# Xedk.net
KiCad netlist of a schematic drawn in Altium Designer
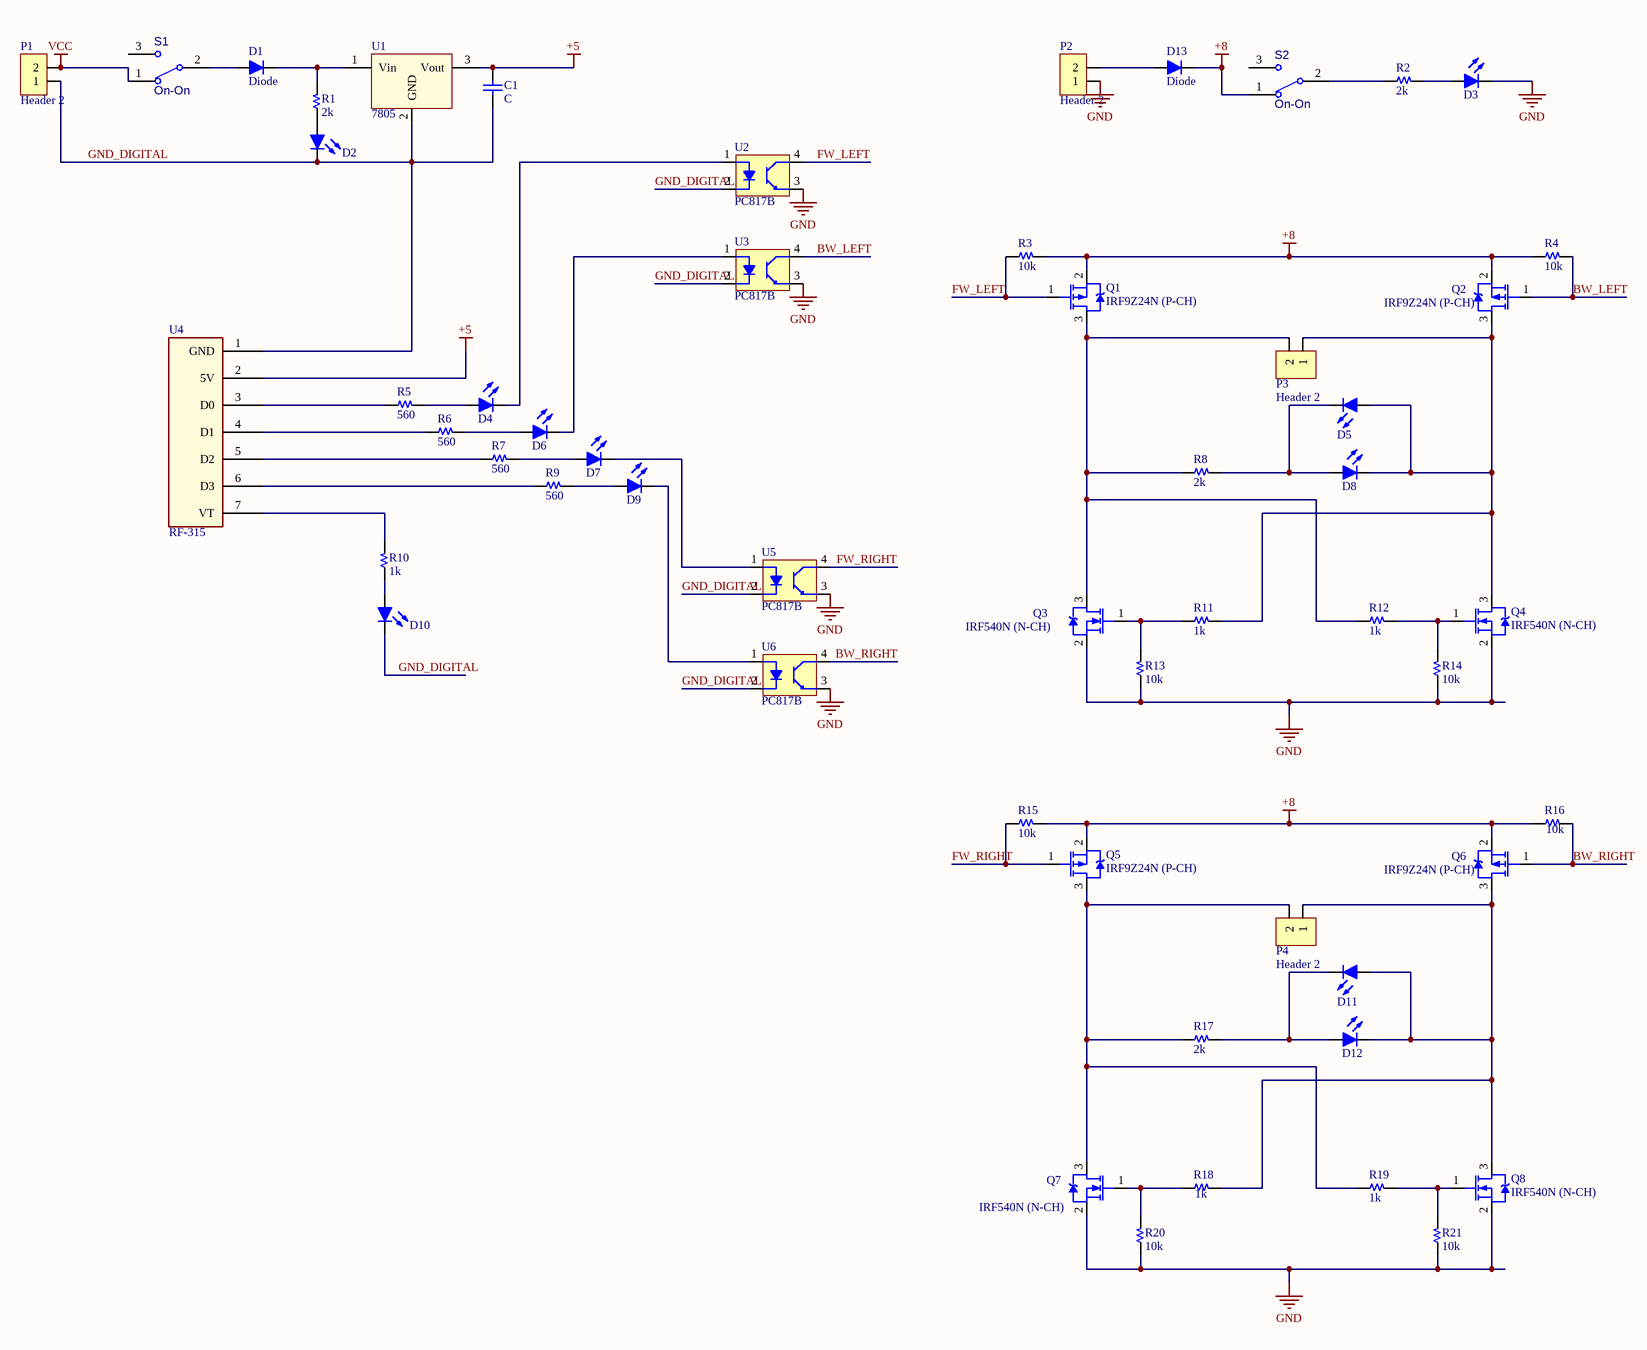
[diagram p0: Xedk.SchDoc]

(export (version "E")
  (design (tool "Eeschema 10.0.6"))
  (components
    (comp (ref "C1")
      (value "C")
      (footprint "CAP Ceramic/W300")
      (description "Capacitor non-pol")
      (libsource (lib "IntLib_Xedk") (part "Capacitor NP"))
    )
    (comp (ref "D1")
      (value "Diode")
      (footprint "DO-41")
      (description "Default Diode")
      (libsource (lib "IntLib_Xedk") (part "Diode"))
    )
    (comp (ref "D2")
      (value "Led")
      (footprint "LED 5MM - GREEN")
      (description "Typical LED")
      (libsource (lib "IntLib_Xedk") (part "Led"))
    )
    (comp (ref "D3")
      (value "Led")
      (footprint "LED 5MM - GREEN")
      (description "Typical LED")
      (libsource (lib "IntLib_Xedk") (part "Led"))
    )
    (comp (ref "D4")
      (value "Led")
      (footprint "LED 5MM - RED")
      (description "Typical LED")
      (libsource (lib "IntLib_Xedk") (part "Led"))
    )
    (comp (ref "D5")
      (value "Led")
      (footprint "LED 5MM - RED")
      (description "Typical LED")
      (libsource (lib "IntLib_Xedk") (part "Led"))
    )
    (comp (ref "D6")
      (value "Led")
      (footprint "LED 5MM - RED")
      (description "Typical LED")
      (libsource (lib "IntLib_Xedk") (part "Led"))
    )
    (comp (ref "D7")
      (value "Led")
      (footprint "LED 5MM - RED")
      (description "Typical LED")
      (libsource (lib "IntLib_Xedk") (part "Led"))
    )
    (comp (ref "D8")
      (value "Led")
      (footprint "LED 5MM - GREEN")
      (description "Typical LED")
      (libsource (lib "IntLib_Xedk") (part "Led"))
    )
    (comp (ref "D9")
      (value "Led")
      (footprint "LED 5MM - RED")
      (description "Typical LED")
      (libsource (lib "IntLib_Xedk") (part "Led"))
    )
    (comp (ref "D10")
      (value "Led")
      (footprint "LED 5MM - RED")
      (description "Typical LED")
      (libsource (lib "IntLib_Xedk") (part "Led"))
    )
    (comp (ref "D11")
      (value "Led")
      (footprint "LED 5MM - RED")
      (description "Typical LED")
      (libsource (lib "IntLib_Xedk") (part "Led"))
    )
    (comp (ref "D12")
      (value "Led")
      (footprint "LED 5MM - GREEN")
      (description "Typical LED")
      (libsource (lib "IntLib_Xedk") (part "Led"))
    )
    (comp (ref "D13")
      (value "Diode")
      (footprint "DO-41")
      (description "Default Diode")
      (libsource (lib "IntLib_Xedk") (part "Diode"))
    )
    (comp (ref "P1")
      (value "Header 2")
      (footprint "HDR/Terminal/2/5mm")
      (description "Header, 2-Pin")
      (libsource (lib "") (part "Header 2_1"))
    )
    (comp (ref "P2")
      (value "Header 2")
      (footprint "HDR/Terminal/2/5mm")
      (description "Header, 2-Pin")
      (libsource (lib "") (part "Header 2_1"))
    )
    (comp (ref "P3")
      (value "Header 2")
      (footprint "HDR/Terminal/2/5mm")
      (description "Header, 2-Pin")
      (libsource (lib "IntLib_Xedk") (part "Header 2"))
    )
    (comp (ref "P4")
      (value "Header 2")
      (footprint "HDR/Terminal/2/5mm")
      (description "Header, 2-Pin")
      (libsource (lib "IntLib_Xedk") (part "Header 2"))
    )
    (comp (ref "Q1")
      (value "IRF9Z24N (P-CH)")
      (footprint "TO-220")
      (description "Mosfet P")
      (libsource (lib "IntLib_Xedk") (part "Mosfet P"))
    )
    (comp (ref "Q2")
      (value "IRF9Z24N (P-CH)")
      (footprint "TO-220")
      (description "Mosfet P")
      (libsource (lib "IntLib_Xedk") (part "Mosfet P"))
    )
    (comp (ref "Q3")
      (value "IRF540N (N-CH)")
      (footprint "TO-220")
      (description "Mosfet N")
      (libsource (lib "IntLib_Xedk") (part "Mosfet N"))
    )
    (comp (ref "Q4")
      (value "IRF540N (N-CH)")
      (footprint "TO-220")
      (description "Mosfet N")
      (libsource (lib "IntLib_Xedk") (part "Mosfet N"))
    )
    (comp (ref "Q5")
      (value "IRF9Z24N (P-CH)")
      (footprint "TO-220")
      (description "Mosfet P")
      (libsource (lib "IntLib_Xedk") (part "Mosfet P"))
    )
    (comp (ref "Q6")
      (value "IRF9Z24N (P-CH)")
      (footprint "TO-220")
      (description "Mosfet P")
      (libsource (lib "IntLib_Xedk") (part "Mosfet P"))
    )
    (comp (ref "Q7")
      (value "IRF540N (N-CH)")
      (footprint "TO-220")
      (description "Mosfet N")
      (libsource (lib "IntLib_Xedk") (part "Mosfet N"))
    )
    (comp (ref "Q8")
      (value "IRF540N (N-CH)")
      (footprint "TO-220")
      (description "Mosfet N")
      (libsource (lib "IntLib_Xedk") (part "Mosfet N"))
    )
    (comp (ref "R1")
      (value "2k")
      (footprint "R 1/4W/300")
      (description "Resistor")
      (libsource (lib "IntLib_Xedk") (part "Resistor"))
    )
    (comp (ref "R2")
      (value "2k")
      (footprint "R 1/4W/300")
      (description "Resistor")
      (libsource (lib "IntLib_Xedk") (part "Resistor"))
    )
    (comp (ref "R3")
      (value "10k")
      (footprint "R 1/4W/300")
      (description "Resistor")
      (libsource (lib "IntLib_Xedk") (part "Resistor"))
    )
    (comp (ref "R4")
      (value "10k")
      (footprint "R 1/4W/300")
      (description "Resistor")
      (libsource (lib "IntLib_Xedk") (part "Resistor"))
    )
    (comp (ref "R5")
      (value "560")
      (footprint "R 1/4W/300")
      (description "Resistor")
      (libsource (lib "IntLib_Xedk") (part "Resistor"))
    )
    (comp (ref "R6")
      (value "560")
      (footprint "R 1/4W/300")
      (description "Resistor")
      (libsource (lib "IntLib_Xedk") (part "Resistor"))
    )
    (comp (ref "R7")
      (value "560")
      (footprint "R 1/4W/300")
      (description "Resistor")
      (libsource (lib "IntLib_Xedk") (part "Resistor"))
    )
    (comp (ref "R8")
      (value "2k")
      (footprint "R 1/4W/300")
      (description "Resistor")
      (libsource (lib "IntLib_Xedk") (part "Resistor"))
    )
    (comp (ref "R9")
      (value "560")
      (footprint "R 1/4W/300")
      (description "Resistor")
      (libsource (lib "IntLib_Xedk") (part "Resistor"))
    )
    (comp (ref "R10")
      (value "1k")
      (footprint "R 1/4W/300")
      (description "Resistor")
      (libsource (lib "IntLib_Xedk") (part "Resistor"))
    )
    (comp (ref "R11")
      (value "1k")
      (footprint "R 1/4W/300")
      (description "Resistor")
      (libsource (lib "IntLib_Xedk") (part "Resistor"))
    )
    (comp (ref "R12")
      (value "1k")
      (footprint "R 1/4W/300")
      (description "Resistor")
      (libsource (lib "IntLib_Xedk") (part "Resistor"))
    )
    (comp (ref "R13")
      (value "10k")
      (footprint "R 1/4W/300")
      (description "Resistor")
      (libsource (lib "IntLib_Xedk") (part "Resistor"))
    )
    (comp (ref "R14")
      (value "10k")
      (footprint "R 1/4W/300")
      (description "Resistor")
      (libsource (lib "IntLib_Xedk") (part "Resistor"))
    )
    (comp (ref "R15")
      (value "10k")
      (footprint "R 1/4W/300")
      (description "Resistor")
      (libsource (lib "IntLib_Xedk") (part "Resistor"))
    )
    (comp (ref "R16")
      (value "10k")
      (footprint "R 1/4W/300")
      (description "Resistor")
      (libsource (lib "IntLib_Xedk") (part "Resistor"))
    )
    (comp (ref "R17")
      (value "2k")
      (footprint "R 1/4W/300")
      (description "Resistor")
      (libsource (lib "IntLib_Xedk") (part "Resistor"))
    )
    (comp (ref "R18")
      (value "1k")
      (footprint "R 1/4W/300")
      (description "Resistor")
      (libsource (lib "IntLib_Xedk") (part "Resistor"))
    )
    (comp (ref "R19")
      (value "1k")
      (footprint "R 1/4W/300")
      (description "Resistor")
      (libsource (lib "IntLib_Xedk") (part "Resistor"))
    )
    (comp (ref "R20")
      (value "10k")
      (footprint "R 1/4W/300")
      (description "Resistor")
      (libsource (lib "IntLib_Xedk") (part "Resistor"))
    )
    (comp (ref "R21")
      (value "10k")
      (footprint "R 1/4W/300")
      (description "Resistor")
      (libsource (lib "IntLib_Xedk") (part "Resistor"))
    )
    (comp (ref "S1")
      (value "ON-ON")
      (footprint "SWITCH_SPDT_SLIDER")
      (description "Switch THD vertical toggle SPDT")
      (fields (field (name "SWITCH FUNCTION") "On-On"))
      (libsource (lib "IntLib_Xedk") (part "SW_THD_SPDT_On-On"))
    )
    (comp (ref "S2")
      (value "ON-ON")
      (footprint "SWITCH_SPDT_SLIDER")
      (description "Switch THD vertical toggle SPDT")
      (fields (field (name "SWITCH FUNCTION") "On-On"))
      (libsource (lib "IntLib_Xedk") (part "SW_THD_SPDT_On-On"))
    )
    (comp (ref "U1")
      (value "7805")
      (footprint "TO-220")
      (description "LDO Fixed Voltage regulator")
      (libsource (lib "IntLib_Xedk") (part "78xx"))
    )
    (comp (ref "U2")
      (value "PC817B")
      (footprint "DIP 4")
      (libsource (lib "IntLib_Xedk") (part "Opto PC817B"))
    )
    (comp (ref "U3")
      (value "PC817B")
      (footprint "DIP 4")
      (libsource (lib "IntLib_Xedk") (part "Opto PC817B"))
    )
    (comp (ref "U4")
      (value "RF-315")
      (footprint "RF-315 7 pins")
      (libsource (lib "IntLib_Xedk") (part "RF-315"))
    )
    (comp (ref "U5")
      (value "PC817B")
      (footprint "DIP 4")
      (libsource (lib "IntLib_Xedk") (part "Opto PC817B"))
    )
    (comp (ref "U6")
      (value "PC817B")
      (footprint "DIP 4")
      (libsource (lib "IntLib_Xedk") (part "Opto PC817B"))
    )
  )
  (nets
    (net (code "1") (name "+5") (class "Default")
      (node (ref "C1") (pin "1") (pinfunction "1_1") (pintype "passive"))
      (node (ref "U1") (pin "3") (pinfunction "Vout_3") (pintype "passive"))
      (node (ref "U4") (pin "2") (pinfunction "5V_2") (pintype "passive"))
    )
    (net (code "2") (name "+8") (class "Default")
      (node (ref "D13") (pin "2") (pinfunction "K_2") (pintype "passive"))
      (node (ref "Q1") (pin "2") (pinfunction "S_2") (pintype "passive"))
      (node (ref "Q2") (pin "2") (pinfunction "S_2") (pintype "passive"))
      (node (ref "Q5") (pin "2") (pinfunction "S_2") (pintype "passive"))
      (node (ref "Q6") (pin "2") (pinfunction "S_2") (pintype "passive"))
      (node (ref "R15") (pin "2") (pinfunction "2_2") (pintype "passive"))
      (node (ref "R16") (pin "1") (pinfunction "1_1") (pintype "passive"))
      (node (ref "R3") (pin "2") (pinfunction "2_2") (pintype "passive"))
      (node (ref "R4") (pin "1") (pinfunction "1_1") (pintype "passive"))
      (node (ref "S2") (pin "1") (pinfunction "1_1") (pintype "passive"))
    )
    (net (code "3") (name "/BW_LEFT") (class "Default")
      (node (ref "Q2") (pin "1") (pinfunction "G_1") (pintype "passive"))
      (node (ref "R4") (pin "2") (pinfunction "2_2") (pintype "passive"))
      (node (ref "U3") (pin "4") (pinfunction "C_4") (pintype "passive"))
    )
    (net (code "4") (name "/BW_RIGHT") (class "Default")
      (node (ref "Q6") (pin "1") (pinfunction "G_1") (pintype "passive"))
      (node (ref "R16") (pin "2") (pinfunction "2_2") (pintype "passive"))
      (node (ref "U6") (pin "4") (pinfunction "C_4") (pintype "passive"))
    )
    (net (code "5") (name "/FW_LEFT") (class "Default")
      (node (ref "Q1") (pin "1") (pinfunction "G_1") (pintype "passive"))
      (node (ref "R3") (pin "1") (pinfunction "1_1") (pintype "passive"))
      (node (ref "U2") (pin "4") (pinfunction "C_4") (pintype "passive"))
    )
    (net (code "6") (name "/FW_RIGHT") (class "Default")
      (node (ref "Q5") (pin "1") (pinfunction "G_1") (pintype "passive"))
      (node (ref "R15") (pin "1") (pinfunction "1_1") (pintype "passive"))
      (node (ref "U5") (pin "4") (pinfunction "C_4") (pintype "passive"))
    )
    (net (code "7") (name "/GND_DIGITAL") (class "Default")
      (node (ref "C1") (pin "2") (pinfunction "2_2") (pintype "passive"))
      (node (ref "D10") (pin "2") (pinfunction "K_2") (pintype "passive"))
      (node (ref "D2") (pin "2") (pinfunction "K_2") (pintype "passive"))
      (node (ref "P1") (pin "1") (pinfunction "1_1") (pintype "passive"))
      (node (ref "U1") (pin "2") (pinfunction "GND_2") (pintype "passive"))
      (node (ref "U2") (pin "2") (pinfunction "K_2") (pintype "passive"))
      (node (ref "U3") (pin "2") (pinfunction "K_2") (pintype "passive"))
      (node (ref "U4") (pin "1") (pinfunction "GND_1") (pintype "passive"))
      (node (ref "U5") (pin "2") (pinfunction "K_2") (pintype "passive"))
      (node (ref "U6") (pin "2") (pinfunction "K_2") (pintype "passive"))
    )
    (net (code "8") (name "GND") (class "Default")
      (node (ref "D3") (pin "2") (pinfunction "K_2") (pintype "passive"))
      (node (ref "P2") (pin "1") (pinfunction "1_1") (pintype "passive"))
      (node (ref "Q3") (pin "2") (pinfunction "S_2") (pintype "passive"))
      (node (ref "Q4") (pin "2") (pinfunction "S_2") (pintype "passive"))
      (node (ref "Q7") (pin "2") (pinfunction "S_2") (pintype "passive"))
      (node (ref "Q8") (pin "2") (pinfunction "S_2") (pintype "passive"))
      (node (ref "R13") (pin "1") (pinfunction "1_1") (pintype "passive"))
      (node (ref "R14") (pin "1") (pinfunction "1_1") (pintype "passive"))
      (node (ref "R20") (pin "1") (pinfunction "1_1") (pintype "passive"))
      (node (ref "R21") (pin "1") (pinfunction "1_1") (pintype "passive"))
      (node (ref "U2") (pin "3") (pinfunction "E_3") (pintype "passive"))
      (node (ref "U3") (pin "3") (pinfunction "E_3") (pintype "passive"))
      (node (ref "U5") (pin "3") (pinfunction "E_3") (pintype "passive"))
      (node (ref "U6") (pin "3") (pinfunction "E_3") (pintype "passive"))
    )
    (net (code "9") (name "Net-(D1-A)") (class "Default")
      (node (ref "D1") (pin "1") (pinfunction "A_1") (pintype "passive"))
      (node (ref "S1") (pin "2") (pinfunction "2_2") (pintype "passive"))
    )
    (net (code "10") (name "Net-(D1-K)") (class "Default")
      (node (ref "D1") (pin "2") (pinfunction "K_2") (pintype "passive"))
      (node (ref "R1") (pin "2") (pinfunction "2_2") (pintype "passive"))
      (node (ref "U1") (pin "1") (pinfunction "Vin_1") (pintype "power_in"))
    )
    (net (code "11") (name "Net-(D2-A)") (class "Default")
      (node (ref "D2") (pin "1") (pinfunction "A_1") (pintype "passive"))
      (node (ref "R1") (pin "1") (pinfunction "1_1") (pintype "passive"))
    )
    (net (code "12") (name "Net-(D3-A)") (class "Default")
      (node (ref "D3") (pin "1") (pinfunction "A_1") (pintype "passive"))
      (node (ref "R2") (pin "2") (pinfunction "2_2") (pintype "passive"))
    )
    (net (code "13") (name "Net-(D4-A)") (class "Default")
      (node (ref "D4") (pin "1") (pinfunction "A_1") (pintype "passive"))
      (node (ref "R5") (pin "2") (pinfunction "2_2") (pintype "passive"))
    )
    (net (code "14") (name "Net-(D4-K)") (class "Default")
      (node (ref "D4") (pin "2") (pinfunction "K_2") (pintype "passive"))
      (node (ref "U2") (pin "1") (pinfunction "A_1") (pintype "passive"))
    )
    (net (code "15") (name "Net-(D5-A)") (class "Default")
      (node (ref "D5") (pin "1") (pinfunction "A_1") (pintype "passive"))
      (node (ref "D8") (pin "2") (pinfunction "K_2") (pintype "passive"))
      (node (ref "P3") (pin "1") (pinfunction "1_1") (pintype "passive"))
      (node (ref "Q2") (pin "3") (pinfunction "D_3") (pintype "passive"))
      (node (ref "Q4") (pin "3") (pinfunction "D_3") (pintype "passive"))
      (node (ref "R11") (pin "2") (pinfunction "2_2") (pintype "passive"))
    )
    (net (code "16") (name "Net-(D5-K)") (class "Default")
      (node (ref "D5") (pin "2") (pinfunction "K_2") (pintype "passive"))
      (node (ref "D8") (pin "1") (pinfunction "A_1") (pintype "passive"))
      (node (ref "R8") (pin "2") (pinfunction "2_2") (pintype "passive"))
    )
    (net (code "17") (name "Net-(D6-A)") (class "Default")
      (node (ref "D6") (pin "1") (pinfunction "A_1") (pintype "passive"))
      (node (ref "R6") (pin "2") (pinfunction "2_2") (pintype "passive"))
    )
    (net (code "18") (name "Net-(D6-K)") (class "Default")
      (node (ref "D6") (pin "2") (pinfunction "K_2") (pintype "passive"))
      (node (ref "U3") (pin "1") (pinfunction "A_1") (pintype "passive"))
    )
    (net (code "19") (name "Net-(D7-A)") (class "Default")
      (node (ref "D7") (pin "1") (pinfunction "A_1") (pintype "passive"))
      (node (ref "R7") (pin "2") (pinfunction "2_2") (pintype "passive"))
    )
    (net (code "20") (name "Net-(D7-K)") (class "Default")
      (node (ref "D7") (pin "2") (pinfunction "K_2") (pintype "passive"))
      (node (ref "U5") (pin "1") (pinfunction "A_1") (pintype "passive"))
    )
    (net (code "21") (name "Net-(D9-A)") (class "Default")
      (node (ref "D9") (pin "1") (pinfunction "A_1") (pintype "passive"))
      (node (ref "R9") (pin "2") (pinfunction "2_2") (pintype "passive"))
    )
    (net (code "22") (name "Net-(D9-K)") (class "Default")
      (node (ref "D9") (pin "2") (pinfunction "K_2") (pintype "passive"))
      (node (ref "U6") (pin "1") (pinfunction "A_1") (pintype "passive"))
    )
    (net (code "23") (name "Net-(D10-A)") (class "Default")
      (node (ref "D10") (pin "1") (pinfunction "A_1") (pintype "passive"))
      (node (ref "R10") (pin "1") (pinfunction "1_1") (pintype "passive"))
    )
    (net (code "24") (name "Net-(D11-A)") (class "Default")
      (node (ref "D11") (pin "1") (pinfunction "A_1") (pintype "passive"))
      (node (ref "D12") (pin "2") (pinfunction "K_2") (pintype "passive"))
      (node (ref "P4") (pin "1") (pinfunction "1_1") (pintype "passive"))
      (node (ref "Q6") (pin "3") (pinfunction "D_3") (pintype "passive"))
      (node (ref "Q8") (pin "3") (pinfunction "D_3") (pintype "passive"))
      (node (ref "R18") (pin "2") (pinfunction "2_2") (pintype "passive"))
    )
    (net (code "25") (name "Net-(D11-K)") (class "Default")
      (node (ref "D11") (pin "2") (pinfunction "K_2") (pintype "passive"))
      (node (ref "D12") (pin "1") (pinfunction "A_1") (pintype "passive"))
      (node (ref "R17") (pin "2") (pinfunction "2_2") (pintype "passive"))
    )
    (net (code "26") (name "Net-(D13-A)") (class "Default")
      (node (ref "D13") (pin "1") (pinfunction "A_1") (pintype "passive"))
      (node (ref "P2") (pin "2") (pinfunction "2_2") (pintype "passive"))
    )
    (net (code "27") (name "Net-(Q1-D)") (class "Default")
      (node (ref "P3") (pin "2") (pinfunction "2_2") (pintype "passive"))
      (node (ref "Q1") (pin "3") (pinfunction "D_3") (pintype "passive"))
      (node (ref "Q3") (pin "3") (pinfunction "D_3") (pintype "passive"))
      (node (ref "R12") (pin "1") (pinfunction "1_1") (pintype "passive"))
      (node (ref "R8") (pin "1") (pinfunction "1_1") (pintype "passive"))
    )
    (net (code "28") (name "Net-(Q3-G)") (class "Default")
      (node (ref "Q3") (pin "1") (pinfunction "G_1") (pintype "passive"))
      (node (ref "R11") (pin "1") (pinfunction "1_1") (pintype "passive"))
      (node (ref "R13") (pin "2") (pinfunction "2_2") (pintype "passive"))
    )
    (net (code "29") (name "Net-(Q4-G)") (class "Default")
      (node (ref "Q4") (pin "1") (pinfunction "G_1") (pintype "passive"))
      (node (ref "R12") (pin "2") (pinfunction "2_2") (pintype "passive"))
      (node (ref "R14") (pin "2") (pinfunction "2_2") (pintype "passive"))
    )
    (net (code "30") (name "Net-(Q5-D)") (class "Default")
      (node (ref "P4") (pin "2") (pinfunction "2_2") (pintype "passive"))
      (node (ref "Q5") (pin "3") (pinfunction "D_3") (pintype "passive"))
      (node (ref "Q7") (pin "3") (pinfunction "D_3") (pintype "passive"))
      (node (ref "R17") (pin "1") (pinfunction "1_1") (pintype "passive"))
      (node (ref "R19") (pin "1") (pinfunction "1_1") (pintype "passive"))
    )
    (net (code "31") (name "Net-(Q7-G)") (class "Default")
      (node (ref "Q7") (pin "1") (pinfunction "G_1") (pintype "passive"))
      (node (ref "R18") (pin "1") (pinfunction "1_1") (pintype "passive"))
      (node (ref "R20") (pin "2") (pinfunction "2_2") (pintype "passive"))
    )
    (net (code "32") (name "Net-(Q8-G)") (class "Default")
      (node (ref "Q8") (pin "1") (pinfunction "G_1") (pintype "passive"))
      (node (ref "R19") (pin "2") (pinfunction "2_2") (pintype "passive"))
      (node (ref "R21") (pin "2") (pinfunction "2_2") (pintype "passive"))
    )
    (net (code "33") (name "Net-(R2-Pad1)") (class "Default")
      (node (ref "R2") (pin "1") (pinfunction "1_1") (pintype "passive"))
      (node (ref "S2") (pin "2") (pinfunction "2_2") (pintype "passive"))
    )
    (net (code "34") (name "Net-(U4-D0)") (class "Default")
      (node (ref "R5") (pin "1") (pinfunction "1_1") (pintype "passive"))
      (node (ref "U4") (pin "3") (pinfunction "D0_3") (pintype "passive"))
    )
    (net (code "35") (name "Net-(U4-D1)") (class "Default")
      (node (ref "R6") (pin "1") (pinfunction "1_1") (pintype "passive"))
      (node (ref "U4") (pin "4") (pinfunction "D1_4") (pintype "passive"))
    )
    (net (code "36") (name "Net-(U4-D2)") (class "Default")
      (node (ref "R7") (pin "1") (pinfunction "1_1") (pintype "passive"))
      (node (ref "U4") (pin "5") (pinfunction "D2_5") (pintype "passive"))
    )
    (net (code "37") (name "Net-(U4-D3)") (class "Default")
      (node (ref "R9") (pin "1") (pinfunction "1_1") (pintype "passive"))
      (node (ref "U4") (pin "6") (pinfunction "D3_6") (pintype "passive"))
    )
    (net (code "38") (name "Net-(U4-VT)") (class "Default")
      (node (ref "R10") (pin "2") (pinfunction "2_2") (pintype "passive"))
      (node (ref "U4") (pin "7") (pinfunction "VT_7") (pintype "passive"))
    )
    (net (code "39") (name "VCC") (class "Default")
      (node (ref "P1") (pin "2") (pinfunction "2_2") (pintype "passive"))
      (node (ref "S1") (pin "1") (pinfunction "1_1") (pintype "passive"))
    )
    (net (code "40") (name "unconnected-(S1-Pad3)") (class "Default")
      (node (ref "S1") (pin "3") (pinfunction "3_3") (pintype "passive"))
    )
    (net (code "41") (name "unconnected-(S2-Pad3)") (class "Default")
      (node (ref "S2") (pin "3") (pinfunction "3_3") (pintype "passive"))
    )
  )
)
